# First_Schematic.net
KiCad netlist of a schematic drawn in Altium Designer
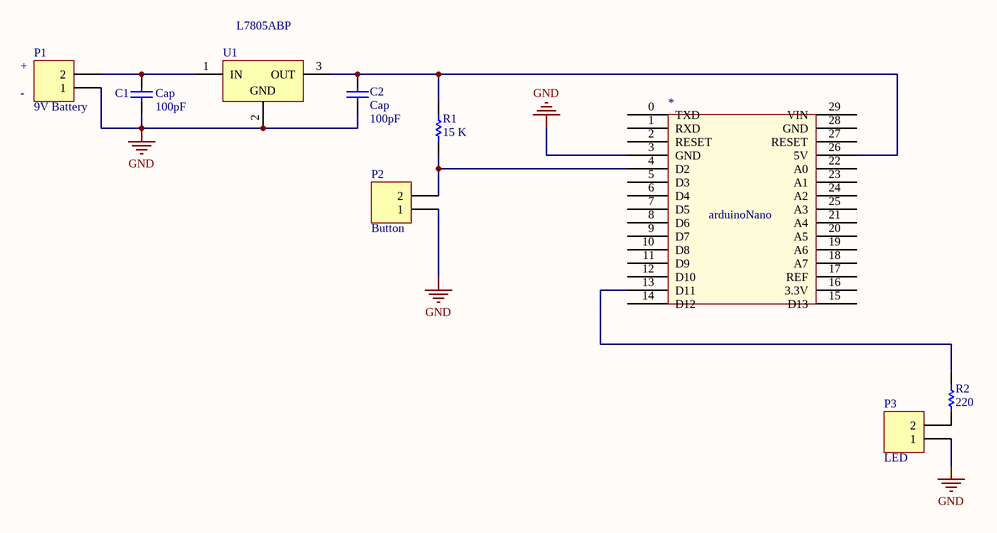
[diagram p0: First_Schematic.SchDoc]

(export (version "E")
  (design (tool "Eeschema 10.0.6"))
  (components
    (comp (ref "*")
      (value "arduinoNano")
      (footprint "Arduino nano")
      (libsource (lib "nanoArduino") (part "arduinoNano"))
    )
    (comp (ref "C1")
      (value "Cap")
      (footprint "RAD-0.3")
      (description "Capacitor")
      (fields (field (name "ALTIUM_VALUE") "100pF") (field (name "PUBLISHER") "Altium Limited"))
      (libsource (lib "Miscellaneous Devices") (part "Cap"))
    )
    (comp (ref "C2")
      (value "Cap")
      (footprint "RAD-0.3")
      (description "Capacitor")
      (fields (field (name "ALTIUM_VALUE") "100pF") (field (name "PUBLISHER") "Altium Limited"))
      (libsource (lib "Miscellaneous Devices") (part "Cap"))
    )
    (comp (ref "P1")
      (value "9V Battery")
      (footprint "HDR1X2")
      (description "Header, 2-Pin")
      (fields (field (name "PUBLISHER") "Altium Limited"))
      (libsource (lib "Miscellaneous Connectors") (part "Header 2"))
    )
    (comp (ref "P2")
      (value "Button")
      (footprint "HDR1X2")
      (description "Header, 2-Pin")
      (fields (field (name "PUBLISHER") "Altium Limited"))
      (libsource (lib "Miscellaneous Connectors") (part "Header 2"))
    )
    (comp (ref "P3")
      (value "LED")
      (footprint "HDR1X2")
      (description "Header, 2-Pin")
      (fields (field (name "PUBLISHER") "Altium Limited"))
      (libsource (lib "Miscellaneous Connectors") (part "Header 2"))
    )
    (comp (ref "R1")
      (value "15 K")
      (footprint "YFDZ-MFJRY13-2_M")
      (fields
        (field (name "PARTNUMBER") "MFJRY13T52051K00")
        (field (name "MANUFACTURER") "YingFa Electronics")
      )
      (libsource (lib "Altium Content Vault") (part "YFDZ-RES-2"))
    )
    (comp (ref "R2")
      (value "220")
      (footprint "YFDZ-MFJRY13-2_M")
      (fields
        (field (name "PARTNUMBER") "MFJRY13T52051K00")
        (field (name "MANUFACTURER") "YingFa Electronics")
      )
      (libsource (lib "Altium Content Vault") (part "YFDZ-RES-2"))
    )
    (comp (ref "U1")
      (value "L7805ABP")
      (footprint "TO220FP")
      (description "Positive Voltage Regulator, 5V, 3-Pin TO-220FP")
      (libsource (lib "Altium Content Vault") (part "PM-REG-L4940-SIL3"))
    )
  )
  (nets
    (net (code "1") (name "GND") (class "Default")
      (node (ref "*") (pin "3") (pinfunction "GND_3") (pintype "passive"))
      (node (ref "C1") (pin "2") (pinfunction "2_2") (pintype "passive"))
      (node (ref "C2") (pin "1") (pinfunction "1_1") (pintype "passive"))
      (node (ref "P1") (pin "1") (pinfunction "1_1") (pintype "passive"))
      (node (ref "P2") (pin "1") (pinfunction "1_1") (pintype "passive"))
      (node (ref "P3") (pin "1") (pinfunction "1_1") (pintype "passive"))
      (node (ref "U1") (pin "2") (pinfunction "GND_2") (pintype "power_in"))
    )
    (net (code "2") (name "Net-(*-5V)") (class "Default")
      (node (ref "*") (pin "26") (pinfunction "5V_26") (pintype "passive"))
      (node (ref "C2") (pin "2") (pinfunction "2_2") (pintype "passive"))
      (node (ref "R1") (pin "2") (pinfunction "2_2") (pintype "passive"))
      (node (ref "U1") (pin "3") (pinfunction "OUT_3") (pintype "power_in"))
    )
    (net (code "3") (name "Net-(*-D2)") (class "Default")
      (node (ref "*") (pin "4") (pinfunction "D2_4") (pintype "passive"))
      (node (ref "P2") (pin "2") (pinfunction "2_2") (pintype "passive"))
      (node (ref "R1") (pin "1") (pinfunction "1_1") (pintype "passive"))
    )
    (net (code "4") (name "Net-(*-D11)") (class "Default")
      (node (ref "*") (pin "13") (pinfunction "D11_13") (pintype "passive"))
      (node (ref "R2") (pin "2") (pinfunction "2_2") (pintype "passive"))
    )
    (net (code "5") (name "Net-(P3-Pad2)") (class "Default")
      (node (ref "P3") (pin "2") (pinfunction "2_2") (pintype "passive"))
      (node (ref "R2") (pin "1") (pinfunction "1_1") (pintype "passive"))
    )
    (net (code "6") (name "Net-(U1-IN)") (class "Default")
      (node (ref "C1") (pin "1") (pinfunction "1_1") (pintype "passive"))
      (node (ref "P1") (pin "2") (pinfunction "2_2") (pintype "passive"))
      (node (ref "U1") (pin "1") (pinfunction "IN_1") (pintype "power_in"))
    )
    (net (code "7") (name "unconnected-(*-3.3V-Pad16)") (class "Default")
      (node (ref "*") (pin "16") (pinfunction "3.3V_16") (pintype "passive"))
    )
    (net (code "8") (name "unconnected-(*-A0-Pad22)") (class "Default")
      (node (ref "*") (pin "22") (pinfunction "A0_22") (pintype "passive"))
    )
    (net (code "9") (name "unconnected-(*-A1-Pad23)") (class "Default")
      (node (ref "*") (pin "23") (pinfunction "A1_23") (pintype "passive"))
    )
    (net (code "10") (name "unconnected-(*-A2-Pad24)") (class "Default")
      (node (ref "*") (pin "24") (pinfunction "A2_24") (pintype "passive"))
    )
    (net (code "11") (name "unconnected-(*-A3-Pad25)") (class "Default")
      (node (ref "*") (pin "25") (pinfunction "A3_25") (pintype "passive"))
    )
    (net (code "12") (name "unconnected-(*-A4-Pad21)") (class "Default")
      (node (ref "*") (pin "21") (pinfunction "A4_21") (pintype "passive"))
    )
    (net (code "13") (name "unconnected-(*-A5-Pad20)") (class "Default")
      (node (ref "*") (pin "20") (pinfunction "A5_20") (pintype "passive"))
    )
    (net (code "14") (name "unconnected-(*-A6-Pad19)") (class "Default")
      (node (ref "*") (pin "19") (pinfunction "A6_19") (pintype "passive"))
    )
    (net (code "15") (name "unconnected-(*-A7-Pad18)") (class "Default")
      (node (ref "*") (pin "18") (pinfunction "A7_18") (pintype "passive"))
    )
    (net (code "16") (name "unconnected-(*-D3-Pad5)") (class "Default")
      (node (ref "*") (pin "5") (pinfunction "D3_5") (pintype "passive"))
    )
    (net (code "17") (name "unconnected-(*-D4-Pad6)") (class "Default")
      (node (ref "*") (pin "6") (pinfunction "D4_6") (pintype "passive"))
    )
    (net (code "18") (name "unconnected-(*-D5-Pad7)") (class "Default")
      (node (ref "*") (pin "7") (pinfunction "D5_7") (pintype "passive"))
    )
    (net (code "19") (name "unconnected-(*-D6-Pad8)") (class "Default")
      (node (ref "*") (pin "8") (pinfunction "D6_8") (pintype "passive"))
    )
    (net (code "20") (name "unconnected-(*-D7-Pad9)") (class "Default")
      (node (ref "*") (pin "9") (pinfunction "D7_9") (pintype "passive"))
    )
    (net (code "21") (name "unconnected-(*-D8-Pad10)") (class "Default")
      (node (ref "*") (pin "10") (pinfunction "D8_10") (pintype "passive"))
    )
    (net (code "22") (name "unconnected-(*-D9-Pad11)") (class "Default")
      (node (ref "*") (pin "11") (pinfunction "D9_11") (pintype "passive"))
    )
    (net (code "23") (name "unconnected-(*-D10-Pad12)") (class "Default")
      (node (ref "*") (pin "12") (pinfunction "D10_12") (pintype "passive"))
    )
    (net (code "24") (name "unconnected-(*-D12-Pad14)") (class "Default")
      (node (ref "*") (pin "14") (pinfunction "D12_14") (pintype "passive"))
    )
    (net (code "25") (name "unconnected-(*-D13-Pad15)") (class "Default")
      (node (ref "*") (pin "15") (pinfunction "D13_15") (pintype "passive"))
    )
    (net (code "26") (name "unconnected-(*-GND-Pad28)") (class "Default")
      (node (ref "*") (pin "28") (pinfunction "GND_28") (pintype "passive"))
    )
    (net (code "27") (name "unconnected-(*-REF-Pad17)") (class "Default")
      (node (ref "*") (pin "17") (pinfunction "REF_17") (pintype "passive"))
    )
    (net (code "28") (name "unconnected-(*-RESET-Pad2)") (class "Default")
      (node (ref "*") (pin "2") (pinfunction "RESET_2") (pintype "passive"))
    )
    (net (code "29") (name "unconnected-(*-RESET-Pad27)") (class "Default")
      (node (ref "*") (pin "27") (pinfunction "RESET_27") (pintype "passive"))
    )
    (net (code "30") (name "unconnected-(*-RXD-Pad1)") (class "Default")
      (node (ref "*") (pin "1") (pinfunction "RXD_1") (pintype "passive"))
    )
    (net (code "31") (name "unconnected-(*-TXD-Pad0)") (class "Default")
      (node (ref "*") (pin "0") (pinfunction "TXD_0") (pintype "passive"))
    )
    (net (code "32") (name "unconnected-(*-VIN-Pad29)") (class "Default")
      (node (ref "*") (pin "29") (pinfunction "VIN_29") (pintype "passive"))
    )
  )
)
